# hr20.net
KiCad netlist of a schematic drawn in EAGLE
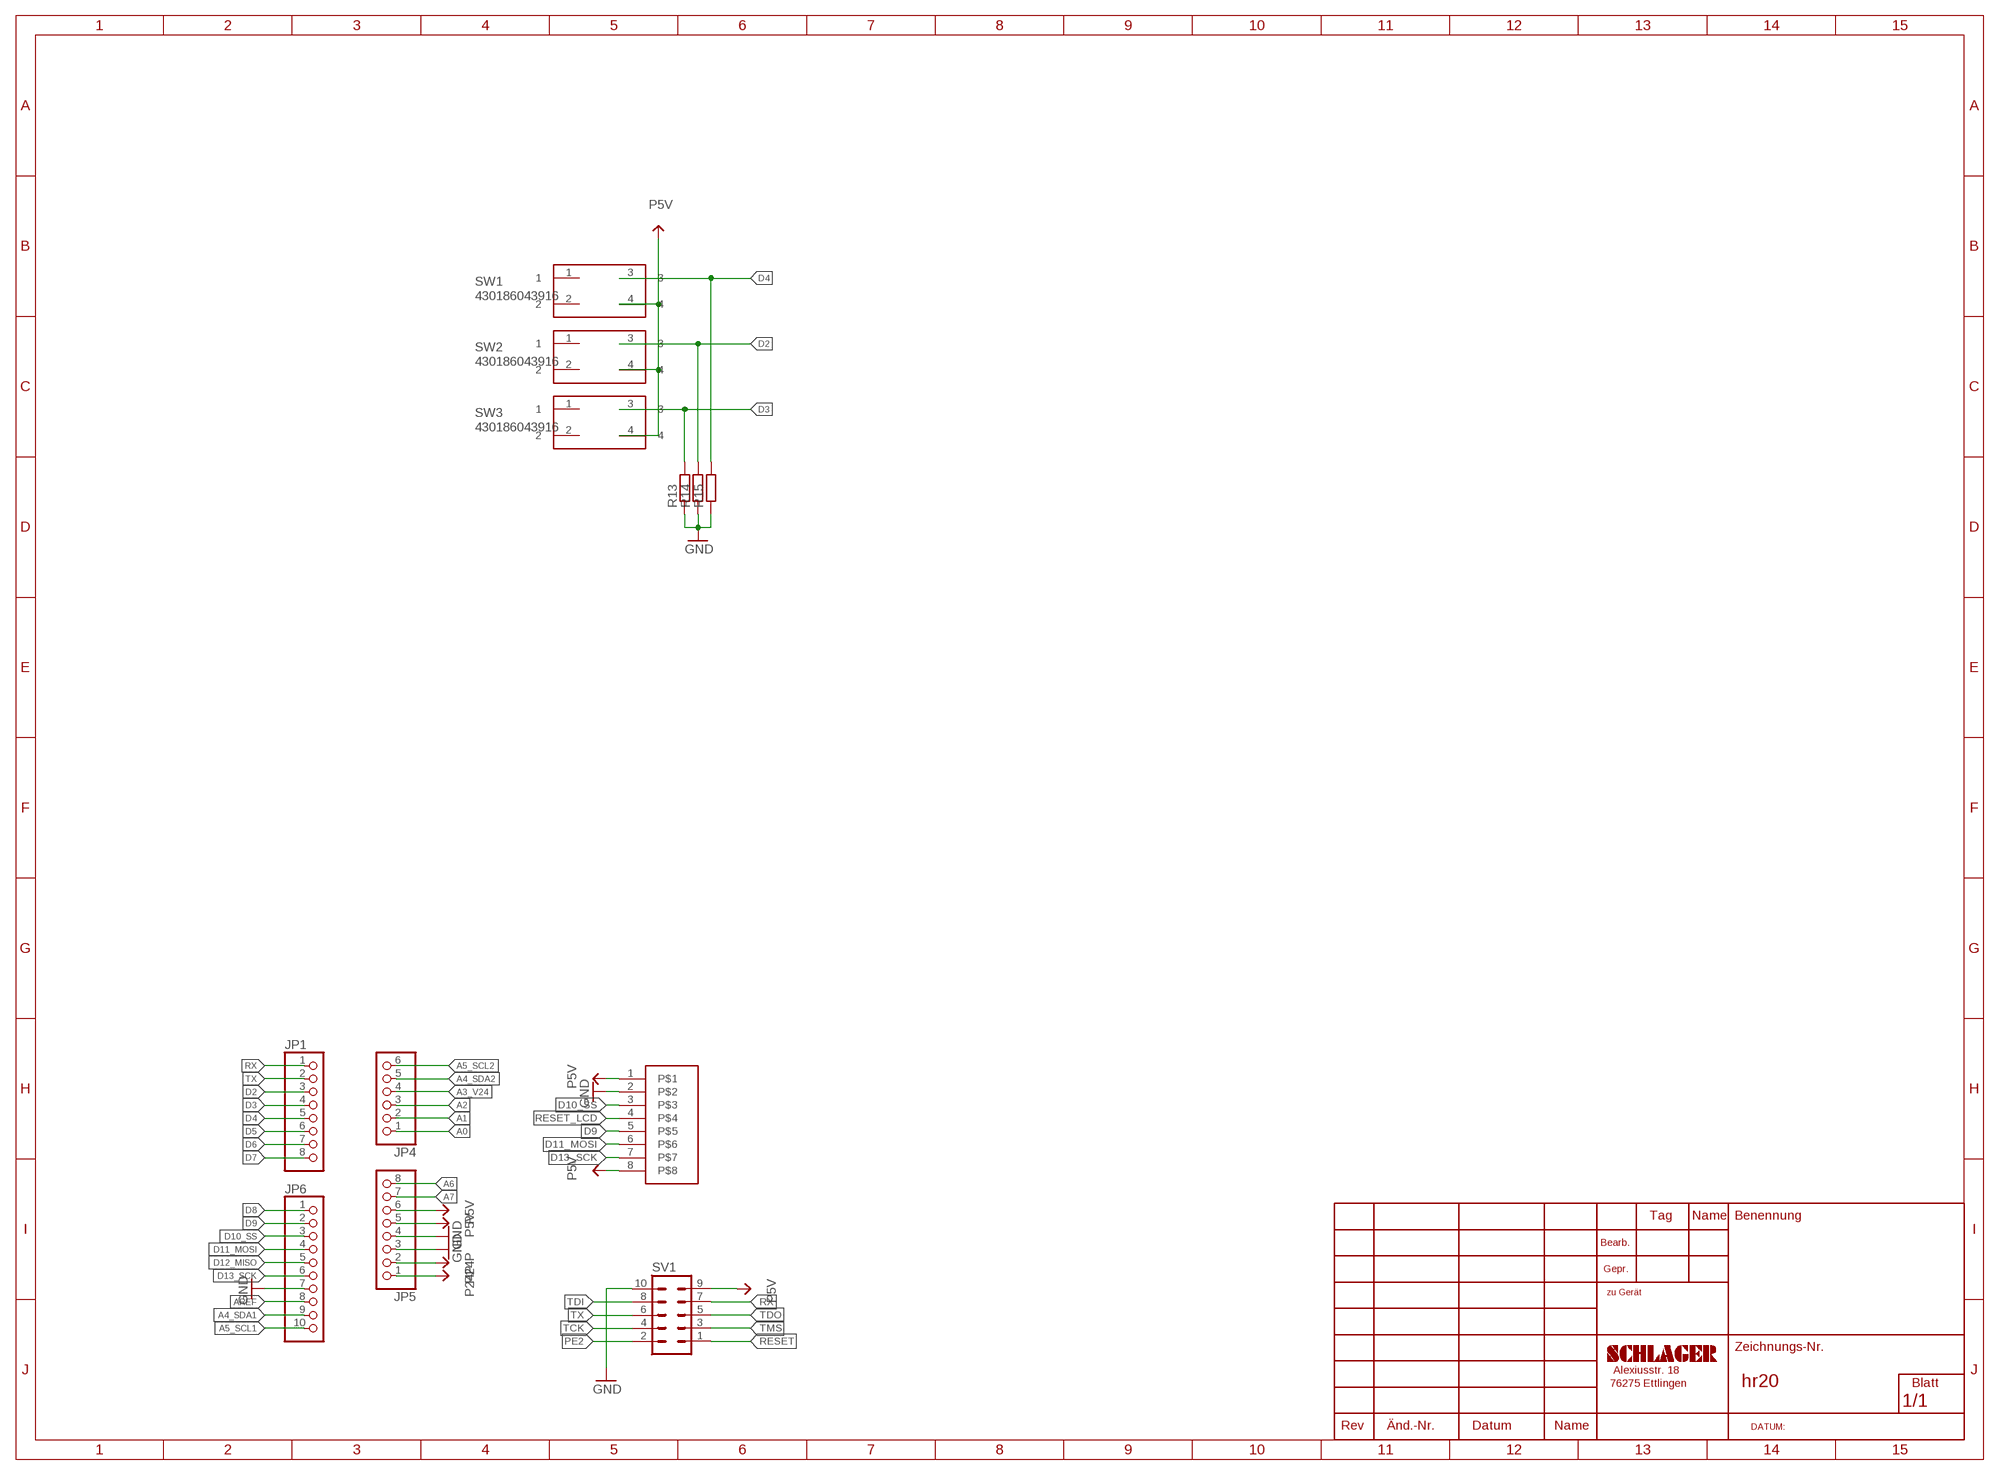
[diagram p0: schematic, sheet 1]

(export (version "E")
  (design (tool "Eeschema 10.0.6"))
  (components
    (comp (ref "JP1")
      (value "PINHD-1X8")
      (footprint "eagle-import:1X08")
      (libsource (lib "eagle-import") (part "PINHD-1X8"))
    )
    (comp (ref "JP4")
      (value "PINHD-1X6")
      (footprint "eagle-import:1X06")
      (libsource (lib "eagle-import") (part "PINHD-1X6"))
    )
    (comp (ref "JP5")
      (value "PINHD-1X8")
      (footprint "eagle-import:1X08")
      (libsource (lib "eagle-import") (part "PINHD-1X8"))
    )
    (comp (ref "JP6")
      (value "PINHD-1X10")
      (footprint "eagle-import:1X10")
      (libsource (lib "eagle-import") (part "PINHD-1X10"))
    )
    (comp (ref "R13")
      (value "R-EU_0207/10")
      (footprint "eagle-import:0207_10")
      (libsource (lib "eagle-import") (part "R-EU_0207/10"))
    )
    (comp (ref "R14")
      (value "R-EU_0207/10")
      (footprint "eagle-import:0207_10")
      (libsource (lib "eagle-import") (part "R-EU_0207/10"))
    )
    (comp (ref "R15")
      (value "R-EU_0207/10")
      (footprint "eagle-import:0207_10")
      (libsource (lib "eagle-import") (part "R-EU_0207/10"))
    )
    (comp (ref "SV1")
      (value "ML10")
      (footprint "eagle-import:ML10")
      (libsource (lib "eagle-import") (part "ML10"))
    )
    (comp (ref "SW1")
      (value "430186043916")
      (footprint "eagle-import:430186043916")
      (libsource (lib "eagle-import") (part "430186043916"))
    )
    (comp (ref "SW2")
      (value "430186043916")
      (footprint "eagle-import:430186043916")
      (libsource (lib "eagle-import") (part "430186043916"))
    )
    (comp (ref "SW3")
      (value "430186043916")
      (footprint "eagle-import:430186043916")
      (libsource (lib "eagle-import") (part "430186043916"))
    )
    (comp (ref "U$2")
      (value "1.44-128X128")
      (footprint "eagle-import:1.44-128X128")
      (libsource (lib "eagle-import") (part "1.44-128X128"))
    )
  )
  (nets
    (net (code "1") (name "A0") (class "Default")
      (node (ref "JP4") (pin "1") (pinfunction "1_1") (pintype "passive"))
    )
    (net (code "2") (name "A1") (class "Default")
      (node (ref "JP4") (pin "2") (pinfunction "2_2") (pintype "passive"))
    )
    (net (code "3") (name "A2") (class "Default")
      (node (ref "JP4") (pin "3") (pinfunction "3_3") (pintype "passive"))
    )
    (net (code "4") (name "A3_V24") (class "Default")
      (node (ref "JP4") (pin "4") (pinfunction "4_4") (pintype "passive"))
    )
    (net (code "5") (name "A4_SDA1") (class "Default")
      (node (ref "JP6") (pin "9") (pinfunction "9_9") (pintype "passive"))
    )
    (net (code "6") (name "A4_SDA2") (class "Default")
      (node (ref "JP4") (pin "5") (pinfunction "5_5") (pintype "passive"))
    )
    (net (code "7") (name "A5_SCL1") (class "Default")
      (node (ref "JP6") (pin "10") (pinfunction "10_10") (pintype "passive"))
    )
    (net (code "8") (name "A5_SCL2") (class "Default")
      (node (ref "JP4") (pin "6") (pinfunction "6_6") (pintype "passive"))
    )
    (net (code "9") (name "A6") (class "Default")
      (node (ref "JP5") (pin "8") (pinfunction "8_8") (pintype "passive"))
    )
    (net (code "10") (name "A7") (class "Default")
      (node (ref "JP5") (pin "7") (pinfunction "7_7") (pintype "passive"))
    )
    (net (code "11") (name "AREF") (class "Default")
      (node (ref "JP6") (pin "8") (pinfunction "8_8") (pintype "passive"))
    )
    (net (code "12") (name "D2") (class "Default")
      (node (ref "JP1") (pin "3") (pinfunction "3_3") (pintype "passive"))
      (node (ref "R14") (pin "2") (pinfunction "2_2") (pintype "passive"))
      (node (ref "SW2") (pin "3") (pinfunction "3_3") (pintype "bidirectional"))
    )
    (net (code "13") (name "D3") (class "Default")
      (node (ref "JP1") (pin "4") (pinfunction "4_4") (pintype "passive"))
      (node (ref "R13") (pin "2") (pinfunction "2_2") (pintype "passive"))
      (node (ref "SW3") (pin "3") (pinfunction "3_3") (pintype "bidirectional"))
    )
    (net (code "14") (name "D4") (class "Default")
      (node (ref "JP1") (pin "5") (pinfunction "5_5") (pintype "passive"))
      (node (ref "R15") (pin "2") (pinfunction "2_2") (pintype "passive"))
      (node (ref "SW1") (pin "3") (pinfunction "3_3") (pintype "bidirectional"))
    )
    (net (code "15") (name "D5") (class "Default")
      (node (ref "JP1") (pin "6") (pinfunction "6_6") (pintype "passive"))
    )
    (net (code "16") (name "D6") (class "Default")
      (node (ref "JP1") (pin "7") (pinfunction "7_7") (pintype "passive"))
    )
    (net (code "17") (name "D7") (class "Default")
      (node (ref "JP1") (pin "8") (pinfunction "8_8") (pintype "passive"))
    )
    (net (code "18") (name "D8") (class "Default")
      (node (ref "JP6") (pin "1") (pinfunction "1_1") (pintype "passive"))
    )
    (net (code "19") (name "D9") (class "Default")
      (node (ref "JP6") (pin "2") (pinfunction "2_2") (pintype "passive"))
      (node (ref "U$2") (pin "5") (pinfunction "P$5_5") (pintype "bidirectional"))
    )
    (net (code "20") (name "D10_SS") (class "Default")
      (node (ref "JP6") (pin "3") (pinfunction "3_3") (pintype "passive"))
      (node (ref "U$2") (pin "3") (pinfunction "P$3_3") (pintype "bidirectional"))
    )
    (net (code "21") (name "D11_MOSI") (class "Default")
      (node (ref "JP6") (pin "4") (pinfunction "4_4") (pintype "passive"))
      (node (ref "U$2") (pin "6") (pinfunction "P$6_6") (pintype "bidirectional"))
    )
    (net (code "22") (name "D12_MISO") (class "Default")
      (node (ref "JP6") (pin "5") (pinfunction "5_5") (pintype "passive"))
    )
    (net (code "23") (name "D13_SCK") (class "Default")
      (node (ref "JP6") (pin "6") (pinfunction "6_6") (pintype "passive"))
      (node (ref "U$2") (pin "7") (pinfunction "P$7_7") (pintype "bidirectional"))
    )
    (net (code "24") (name "GND") (class "Default")
      (node (ref "JP5") (pin "3") (pinfunction "3_3") (pintype "passive"))
      (node (ref "JP5") (pin "4") (pinfunction "4_4") (pintype "passive"))
      (node (ref "JP6") (pin "7") (pinfunction "7_7") (pintype "passive"))
      (node (ref "R13") (pin "1") (pinfunction "1_1") (pintype "passive"))
      (node (ref "R14") (pin "1") (pinfunction "1_1") (pintype "passive"))
      (node (ref "R15") (pin "1") (pinfunction "1_1") (pintype "passive"))
      (node (ref "SV1") (pin "10") (pinfunction "10_10") (pintype "passive"))
      (node (ref "U$2") (pin "2") (pinfunction "P$2_2") (pintype "bidirectional"))
    )
    (net (code "25") (name "P5V") (class "Default")
      (node (ref "JP5") (pin "5") (pinfunction "5_5") (pintype "passive"))
      (node (ref "JP5") (pin "6") (pinfunction "6_6") (pintype "passive"))
      (node (ref "SV1") (pin "9") (pinfunction "9_9") (pintype "passive"))
      (node (ref "SW1") (pin "4") (pinfunction "4_4") (pintype "bidirectional"))
      (node (ref "SW2") (pin "4") (pinfunction "4_4") (pintype "bidirectional"))
      (node (ref "SW3") (pin "4") (pinfunction "4_4") (pintype "bidirectional"))
      (node (ref "U$2") (pin "1") (pinfunction "P$1_1") (pintype "bidirectional"))
      (node (ref "U$2") (pin "8") (pinfunction "P$8_8") (pintype "bidirectional"))
    )
    (net (code "26") (name "P24P") (class "Default")
      (node (ref "JP5") (pin "1") (pinfunction "1_1") (pintype "passive"))
      (node (ref "JP5") (pin "2") (pinfunction "2_2") (pintype "passive"))
    )
    (net (code "27") (name "PE2") (class "Default")
      (node (ref "SV1") (pin "2") (pinfunction "2_2") (pintype "passive"))
    )
    (net (code "28") (name "RESET") (class "Default")
      (node (ref "SV1") (pin "1") (pinfunction "1_1") (pintype "passive"))
    )
    (net (code "29") (name "RESET_LCD") (class "Default")
      (node (ref "U$2") (pin "4") (pinfunction "P$4_4") (pintype "bidirectional"))
    )
    (net (code "30") (name "RX") (class "Default")
      (node (ref "JP1") (pin "1") (pinfunction "1_1") (pintype "passive"))
      (node (ref "SV1") (pin "7") (pinfunction "7_7") (pintype "passive"))
    )
    (net (code "31") (name "TCK") (class "Default")
      (node (ref "SV1") (pin "4") (pinfunction "4_4") (pintype "passive"))
    )
    (net (code "32") (name "TDI") (class "Default")
      (node (ref "SV1") (pin "8") (pinfunction "8_8") (pintype "passive"))
    )
    (net (code "33") (name "TDO") (class "Default")
      (node (ref "SV1") (pin "5") (pinfunction "5_5") (pintype "passive"))
    )
    (net (code "34") (name "TMS") (class "Default")
      (node (ref "SV1") (pin "3") (pinfunction "3_3") (pintype "passive"))
    )
    (net (code "35") (name "TX") (class "Default")
      (node (ref "JP1") (pin "2") (pinfunction "2_2") (pintype "passive"))
      (node (ref "SV1") (pin "6") (pinfunction "6_6") (pintype "passive"))
    )
    (net (code "36") (name "unconnected-(SW1-Pad1)") (class "Default")
      (node (ref "SW1") (pin "1") (pinfunction "1_1") (pintype "bidirectional"))
    )
    (net (code "37") (name "unconnected-(SW1-Pad2)") (class "Default")
      (node (ref "SW1") (pin "2") (pinfunction "2_2") (pintype "bidirectional"))
    )
    (net (code "38") (name "unconnected-(SW2-Pad1)") (class "Default")
      (node (ref "SW2") (pin "1") (pinfunction "1_1") (pintype "bidirectional"))
    )
    (net (code "39") (name "unconnected-(SW2-Pad2)") (class "Default")
      (node (ref "SW2") (pin "2") (pinfunction "2_2") (pintype "bidirectional"))
    )
    (net (code "40") (name "unconnected-(SW3-Pad1)") (class "Default")
      (node (ref "SW3") (pin "1") (pinfunction "1_1") (pintype "bidirectional"))
    )
    (net (code "41") (name "unconnected-(SW3-Pad2)") (class "Default")
      (node (ref "SW3") (pin "2") (pinfunction "2_2") (pintype "bidirectional"))
    )
  )
)
